# Power.net
KiCad netlist of a schematic drawn in Altium Designer
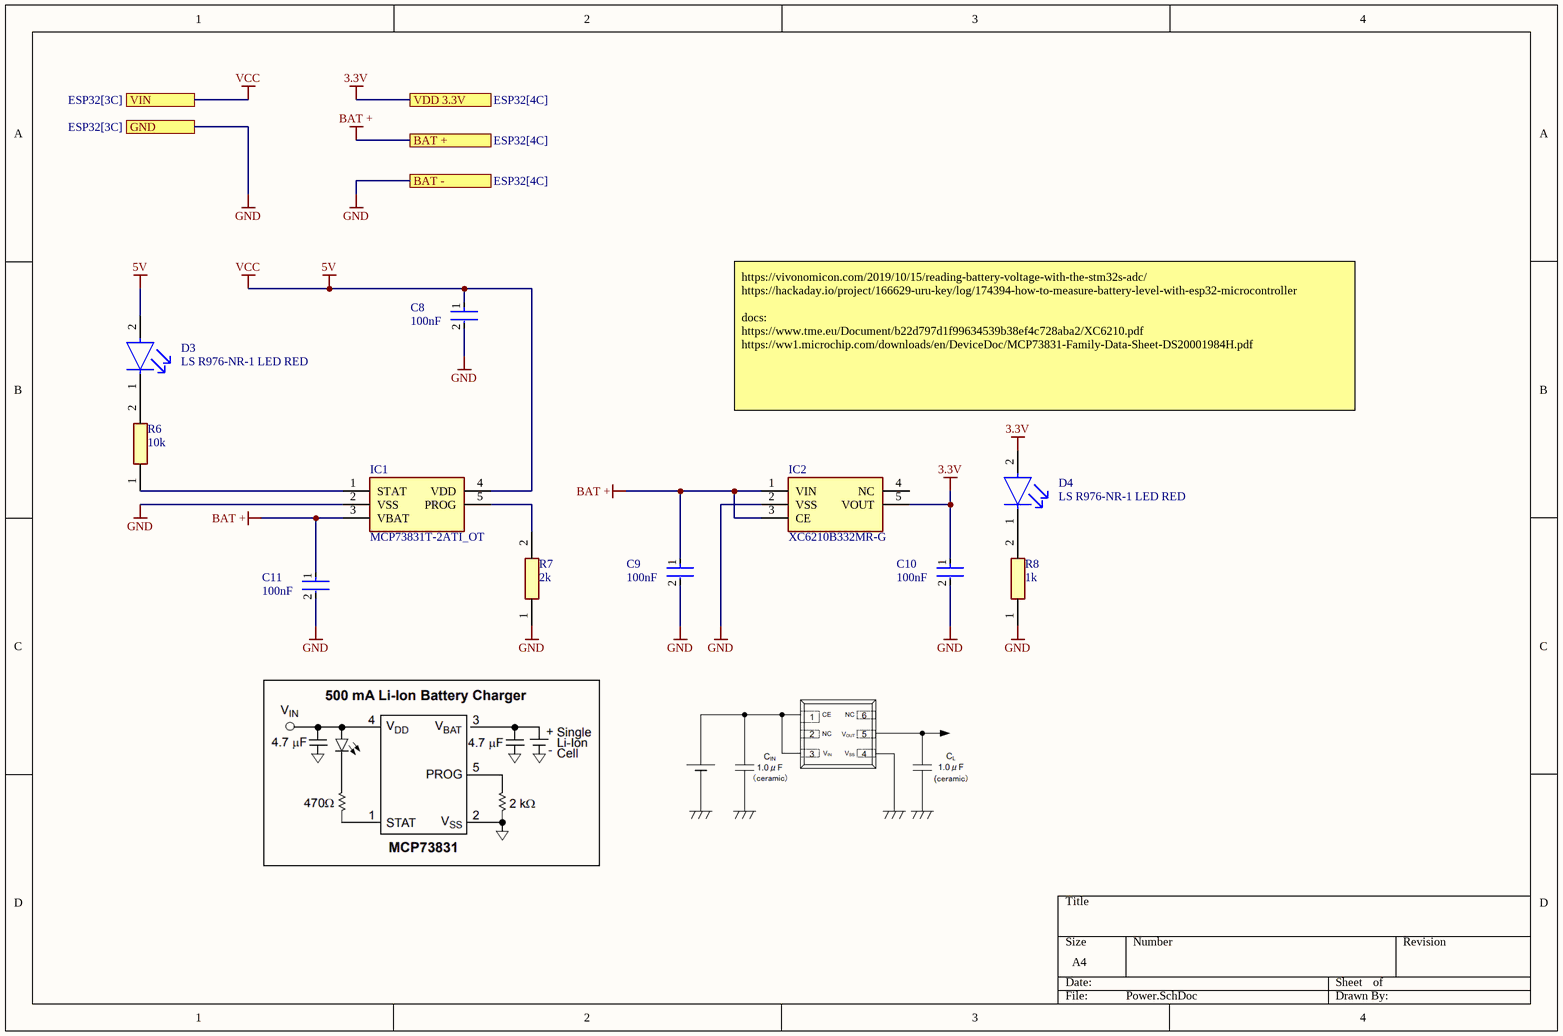
[diagram p0: Power.SchDoc]

(export (version "E")
  (design (tool "Eeschema 10.0.6"))
  (components
    (comp (ref "C8")
      (value "100nF")
      (footprint "FP-0805-L_2_01_0_2-W_1_25-MFG")
      (description "Automotive Ceramic Capacitor, 0805, 100nF, 5%, X7R, 15%, 100V")
      (fields (field (name "TOLERANCE") "5%"))
      (libsource (lib "Altium Content Vault") (part "b4654b650e69147ec39a6b967a45e02"))
    )
    (comp (ref "C9")
      (value "100nF")
      (footprint "FP-0805-L_2_01_0_2-W_1_25-MFG")
      (description "Automotive Ceramic Capacitor, 0805, 100nF, 5%, X7R, 15%, 100V")
      (fields (field (name "TOLERANCE") "5%"))
      (libsource (lib "Altium Content Vault") (part "b4654b650e69147ec39a6b967a45e02"))
    )
    (comp (ref "C10")
      (value "100nF")
      (footprint "FP-0805-L_2_01_0_2-W_1_25-MFG")
      (description "Automotive Ceramic Capacitor, 0805, 100nF, 5%, X7R, 15%, 100V")
      (fields (field (name "TOLERANCE") "5%"))
      (libsource (lib "Altium Content Vault") (part "b4654b650e69147ec39a6b967a45e02"))
    )
    (comp (ref "C11")
      (value "100nF")
      (footprint "FP-0805-L_2_01_0_2-W_1_25-MFG")
      (description "Automotive Ceramic Capacitor, 0805, 100nF, 5%, X7R, 15%, 100V")
      (fields (field (name "TOLERANCE") "5%"))
      (libsource (lib "Altium Content Vault") (part "b4654b650e69147ec39a6b967a45e02"))
    )
    (comp (ref "D3")
      (value "LS R976-NR-1 LED RED")
      (footprint "FP-LS_R976-MFG")
      (description "LED RED DIFFUSED 0805 SMD")
      (libsource (lib "Altium Content Vault") (part "8706943c75ba83719d021d2fdc84c58"))
    )
    (comp (ref "D4")
      (value "LS R976-NR-1 LED RED")
      (footprint "FP-LS_R976-MFG")
      (description "LED RED DIFFUSED 0805 SMD")
      (libsource (lib "Altium Content Vault") (part "8706943c75ba83719d021d2fdc84c58"))
    )
    (comp (ref "IC1")
      (value "MCP73831T-2ATI_OT")
      (footprint "SamacSys:SOT95P270X145-5N")
      (description "Integrated Circuit")
      (fields
        (field (name "MANUFACTURER_PART_NUMBER") "MCP73831T-2ATI/OT")
        (field (name "MOUSER PART NUMBER") "579-MCP73831T-2ATIOT")
      )
      (libsource (lib "*") (part "MCP73831T-2ATI_OT"))
    )
    (comp (ref "IC2")
      (value "XC6210B332MR-G")
      (footprint "SamacSys:SOT95P280X130-5N")
      (description "Integrated Circuit")
      (fields (field (name "MOUSER PART NUMBER") "865-XC6210B332MR-G"))
      (libsource (lib "SamacSys") (part "XC6210B332MR-G"))
    )
    (comp (ref "R6")
      (value "10k")
      (footprint "SamacSys:RESC2013X65N")
      (description "Resistor")
      (fields (field (name "MANUFACTURER_PART_NUMBER") "0805W8F1000T5E"))
      (libsource (lib "*") (part "0805W8F1000T5E"))
    )
    (comp (ref "R7")
      (value "2k")
      (footprint "SamacSys:RESC2013X65N")
      (description "Resistor")
      (fields (field (name "MANUFACTURER_PART_NUMBER") "0805W8F1000T5E"))
      (libsource (lib "*") (part "0805W8F1000T5E"))
    )
    (comp (ref "R8")
      (value "1k")
      (footprint "SamacSys:RESC2013X65N")
      (description "Resistor")
      (fields (field (name "MANUFACTURER_PART_NUMBER") "0805W8F1000T5E"))
      (libsource (lib "*") (part "0805W8F1000T5E"))
    )
  )
  (nets
    (net (code "1") (name "3.3V") (class "Default")
      (node (ref "C10") (pin "1") (pinfunction "1_1") (pintype "passive"))
      (node (ref "D4") (pin "2") (pinfunction "A_2") (pintype "passive"))
      (node (ref "IC2") (pin "5") (pinfunction "VOUT_5") (pintype "passive"))
    )
    (net (code "2") (name "5V") (class "Default")
      (node (ref "C8") (pin "1") (pinfunction "1_1") (pintype "passive"))
      (node (ref "D3") (pin "2") (pinfunction "A_2") (pintype "passive"))
      (node (ref "IC1") (pin "4") (pinfunction "VDD_4") (pintype "passive"))
    )
    (net (code "3") (name "BAT +") (class "Default")
      (node (ref "C11") (pin "1") (pinfunction "1_1") (pintype "passive"))
      (node (ref "C9") (pin "1") (pinfunction "1_1") (pintype "passive"))
      (node (ref "IC1") (pin "3") (pinfunction "VBAT_3") (pintype "passive"))
      (node (ref "IC2") (pin "1") (pinfunction "VIN_1") (pintype "passive"))
      (node (ref "IC2") (pin "3") (pinfunction "CE_3") (pintype "passive"))
    )
    (net (code "4") (name "GND") (class "Default")
      (node (ref "C10") (pin "2") (pinfunction "2_2") (pintype "passive"))
      (node (ref "C11") (pin "2") (pinfunction "2_2") (pintype "passive"))
      (node (ref "C8") (pin "2") (pinfunction "2_2") (pintype "passive"))
      (node (ref "C9") (pin "2") (pinfunction "2_2") (pintype "passive"))
      (node (ref "IC1") (pin "2") (pinfunction "VSS_2") (pintype "passive"))
      (node (ref "IC2") (pin "2") (pinfunction "VSS_2") (pintype "passive"))
      (node (ref "R7") (pin "1") (pinfunction "1_1") (pintype "passive"))
      (node (ref "R8") (pin "1") (pinfunction "1_1") (pintype "passive"))
    )
    (net (code "5") (name "Net-(D3-C)") (class "Default")
      (node (ref "D3") (pin "1") (pinfunction "C_1") (pintype "passive"))
      (node (ref "R6") (pin "2") (pinfunction "2_2") (pintype "passive"))
    )
    (net (code "6") (name "Net-(D4-C)") (class "Default")
      (node (ref "D4") (pin "1") (pinfunction "C_1") (pintype "passive"))
      (node (ref "R8") (pin "2") (pinfunction "2_2") (pintype "passive"))
    )
    (net (code "7") (name "Net-(IC1-PROG)") (class "Default")
      (node (ref "IC1") (pin "5") (pinfunction "PROG_5") (pintype "passive"))
      (node (ref "R7") (pin "2") (pinfunction "2_2") (pintype "passive"))
    )
    (net (code "8") (name "Net-(IC1-STAT)") (class "Default")
      (node (ref "IC1") (pin "1") (pinfunction "STAT_1") (pintype "passive"))
      (node (ref "R6") (pin "1") (pinfunction "1_1") (pintype "passive"))
    )
    (net (code "9") (name "unconnected-(IC2-NC-Pad4)") (class "Default")
      (node (ref "IC2") (pin "4") (pinfunction "NC_4") (pintype "passive"))
    )
  )
)
